# MotorSurucu.net
KiCad netlist of a schematic drawn in Altium Designer
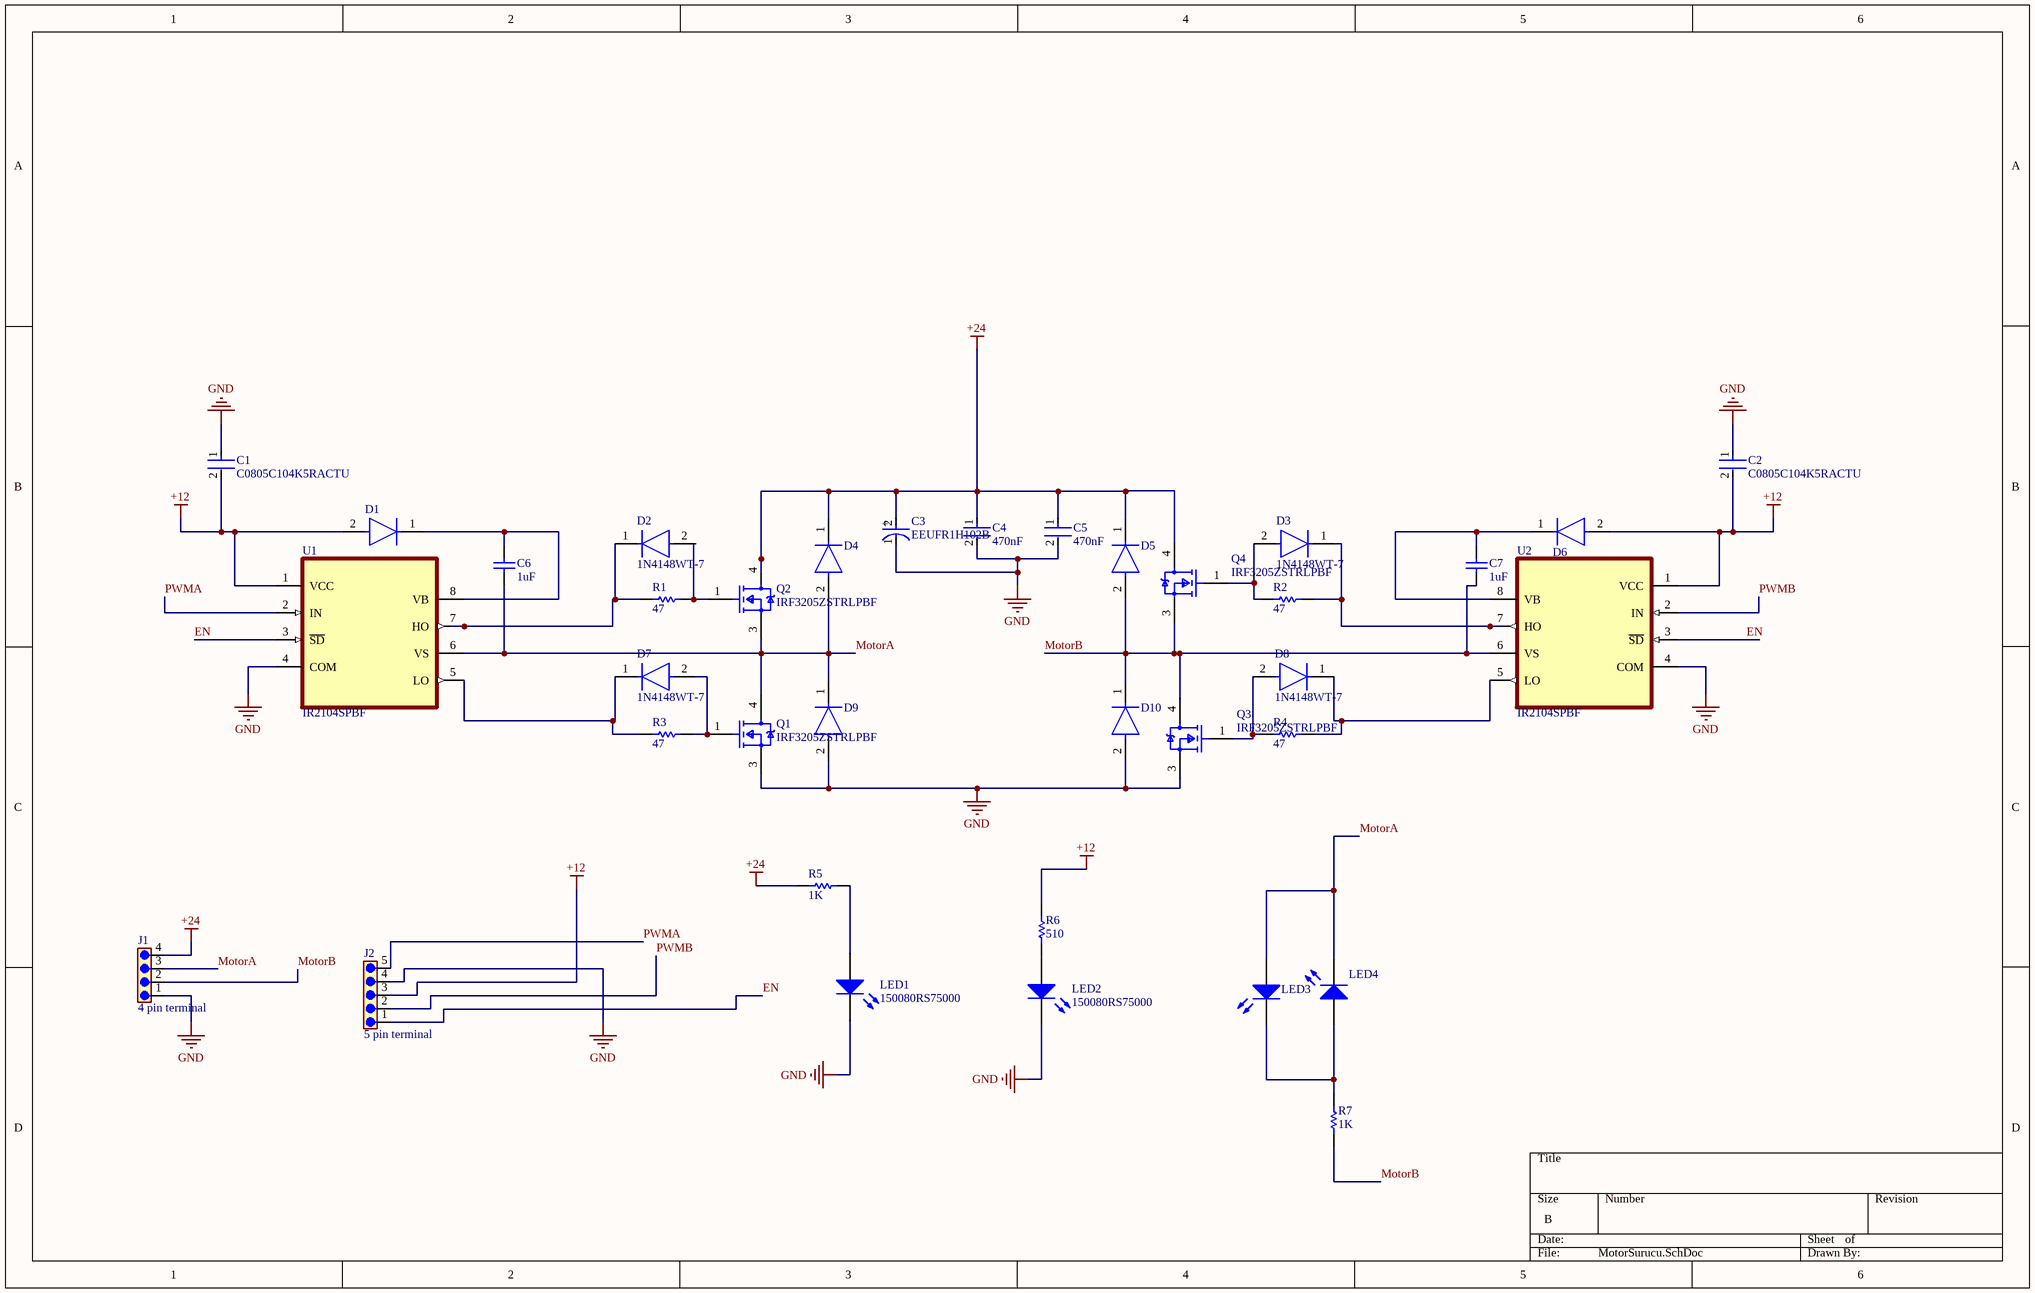
[diagram p0: MotorSurucu.SchDoc]

(export (version "E")
  (design (tool "Eeschema 10.0.6"))
  (components
    (comp (ref "C1")
      (value "C0805C104K5RACTU")
      (footprint "FP-C0805C-DN-MFG")
      (description "CAP CER 0.1UF 50V X7R 0805")
      (fields
        (field (name "MANUFACTURER") "KEMET")
        (field (name "OCTOPART") "https://octopart.com/c0805c104k5ractu-kemet-143926")
      )
      (libsource (lib "Altium Content Vault") (part "b4654b650e69147ec39a6b967a45e02"))
    )
    (comp (ref "C2")
      (value "C0805C104K5RACTU")
      (footprint "FP-C0805C-DN-MFG")
      (description "CAP CER 0.1UF 50V X7R 0805")
      (fields
        (field (name "MANUFACTURER") "KEMET")
        (field (name "OCTOPART") "https://octopart.com/c0805c104k5ractu-kemet-143926")
      )
      (libsource (lib "Altium Content Vault") (part "b4654b650e69147ec39a6b967a45e02"))
    )
    (comp (ref "C3")
      (value "EEUFR1H102B")
      (footprint "FP-RAD-TH-D_16_0_5-L_25_2-MFG")
      (description "Aluminum Electrolytic Capacitors (Radial Lead Type) 1000uF ±20% 50V")
      (fields (field (name "TOLERANCE") "20%"))
      (libsource (lib "Altium Content Vault") (part "203bc49f2ac43e59fd269a8c329ed05"))
    )
    (comp (ref "C4")
      (value "470nF")
      (footprint "FP-C0805C-DN-MFG")
      (description "CAP CER 0.47UF 50V 10% X7R 0805 C0805C474K5RACTU")
      (fields
        (field (name "MANUFACTURER") "KEMET")
        (field (name "MANUFACTURER PART NUMBER") "C0805C474K5RACTU")
      )
      (libsource (lib "Altium Content Vault") (part "b4654b650e69147ec39a6b967a45e02"))
    )
    (comp (ref "C5")
      (value "470nF")
      (footprint "FP-C0805C-DN-MFG")
      (description "CAP CER 0.47UF 50V 10% X7R 0805 C0805C474K5RACTU")
      (fields
        (field (name "MANUFACTURER") "KEMET")
        (field (name "MANUFACTURER PART NUMBER") "C0805C474K5RACTU")
      )
      (libsource (lib "Altium Content Vault") (part "b4654b650e69147ec39a6b967a45e02"))
    )
    (comp (ref "C6")
      (value "1uF")
      (footprint "CAPC2013X135X45LL10T25")
      (description "GRM21BR71H105KA12L")
      (fields (field (name "MANUFACTURER") "Murata"))
      (libsource (lib "Altium Content Vault") (part "CAP"))
    )
    (comp (ref "C7")
      (value "1uF")
      (footprint "CAPC2013X135X45LL10T25")
      (description "GRM21BR71H105KA12L    0805")
      (fields (field (name "MANUFACTURER") "Murata") (field (name "PART NUMBER") "GRM21BR71H105KA12L"))
      (libsource (lib "Altium Content Vault") (part "CAP"))
    )
    (comp (ref "D1")
      (value "1N5819HW1-7-F")
      (footprint "FP-SOD123F_Type_B-MFG")
      (description "DIODE SBR 40V 1A SOD123F")
      (fields
        (field (name "MANUFACTURER") "Diodes Inc.")
        (field (name "OCTOPART") "https://octopart.com/1n5819hw1-7-f-diodes+inc.-67250096")
      )
      (libsource (lib "Altium Content Vault") (part "d7152d700b627762746794eb795d46e"))
    )
    (comp (ref "D2")
      (value "1N4148WT-7")
      (footprint "FP-SOD523-MFG")
      (description "DIODE GEN PURP 80V 125MA SOD523")
      (libsource (lib "Altium Content Vault") (part "d7152d700b627762746794eb795d46e"))
    )
    (comp (ref "D3")
      (value "1N4148WT-7")
      (footprint "FP-SOD523-MFG")
      (description "DIODE GEN PURP 80V 125MA SOD523")
      (libsource (lib "Altium Content Vault") (part "d7152d700b627762746794eb795d46e"))
    )
    (comp (ref "D4")
      (value "1N5819HW1-7-F")
      (footprint "FP-SOD123F_Type_B-MFG")
      (description "DIODE SBR 40V 1A SOD123F")
      (fields
        (field (name "MANUFACTURER") "Diodes Inc.")
        (field (name "OCTOPART") "https://octopart.com/1n5819hw1-7-f-diodes+inc.-67250096")
      )
      (libsource (lib "Altium Content Vault") (part "d7152d700b627762746794eb795d46e"))
    )
    (comp (ref "D5")
      (value "1N5819HW1-7-F")
      (footprint "FP-SOD123F_Type_B-MFG")
      (description "DIODE SBR 40V 1A SOD123F")
      (fields
        (field (name "MANUFACTURER") "Diodes Inc.")
        (field (name "OCTOPART") "https://octopart.com/1n5819hw1-7-f-diodes+inc.-67250096")
      )
      (libsource (lib "Altium Content Vault") (part "d7152d700b627762746794eb795d46e"))
    )
    (comp (ref "D6")
      (value "1N5819HW1-7-F")
      (footprint "FP-SOD123F_Type_B-MFG")
      (description "DIODE SBR 40V 1A SOD123F")
      (fields
        (field (name "MANUFACTURER") "Diodes Inc.")
        (field (name "OCTOPART") "https://octopart.com/1n5819hw1-7-f-diodes+inc.-67250096")
      )
      (libsource (lib "Altium Content Vault") (part "d7152d700b627762746794eb795d46e"))
    )
    (comp (ref "D7")
      (value "1N4148WT-7")
      (footprint "FP-SOD523-MFG")
      (description "DIODE GEN PURP 80V 125MA SOD523")
      (libsource (lib "Altium Content Vault") (part "d7152d700b627762746794eb795d46e"))
    )
    (comp (ref "D8")
      (value "1N4148WT-7")
      (footprint "FP-SOD523-MFG")
      (description "DIODE GEN PURP 80V 125MA SOD523")
      (libsource (lib "Altium Content Vault") (part "d7152d700b627762746794eb795d46e"))
    )
    (comp (ref "D9")
      (value "1N5819HW1-7-F")
      (footprint "FP-SOD123F_Type_B-MFG")
      (description "DIODE SBR 40V 1A SOD123F")
      (fields
        (field (name "MANUFACTURER") "Diodes Inc.")
        (field (name "OCTOPART") "https://octopart.com/1n5819hw1-7-f-diodes+inc.-67250096")
      )
      (libsource (lib "Altium Content Vault") (part "d7152d700b627762746794eb795d46e"))
    )
    (comp (ref "D10")
      (value "1N5819HW1-7-F")
      (footprint "FP-SOD123F_Type_B-MFG")
      (description "DIODE SBR 40V 1A SOD123F")
      (fields
        (field (name "MANUFACTURER") "Diodes Inc.")
        (field (name "OCTOPART") "https://octopart.com/1n5819hw1-7-f-diodes+inc.-67250096")
      )
      (libsource (lib "Altium Content Vault") (part "d7152d700b627762746794eb795d46e"))
    )
    (comp (ref "J1")
      (value "4 pin terminal")
      (footprint "yesil klemens disi")
      (description "WR-TBL SERIES 3055_5.08 MM_PCB H")
      (fields (field (name "MF") "WÃ¼rth Elektronik") (field (name "MP") "691305530004"))
      (libsource (lib "Yildiz_Rover") (part "yesil klemens disi"))
    )
    (comp (ref "J2")
      (value "5 pin terminal")
      (footprint "5li klemens disi")
      (libsource (lib "Yildiz_Rover") (part "5li klemens disi"))
    )
    (comp (ref "LED1")
      (value "150080RS75000")
      (footprint "0805_A")
      (description "SMD mono-color Chip LED, WL-SMCW, Red")
      (fields (field (name "MANUFACTURER") "Wuerth Elektronik"))
      (libsource (lib "Altium Content Vault") (part "WE-LED_K1A2-2"))
    )
    (comp (ref "LED2")
      (value "150080RS75000")
      (footprint "0805_A")
      (description "SMD mono-color Chip LED, WL-SMCW, Red")
      (fields (field (name "MANUFACTURER") "Wuerth Elektronik"))
      (libsource (lib "Altium Content Vault") (part "WE-LED_K1A2-2"))
    )
    (comp (ref "LED3")
      (value "150080BS75000")
      (footprint "0805_A")
      (description "SMD mono-color Chip LED, WL-SMCW, Blue")
      (fields (field (name "MANUFACTURER") "Wuerth Elektronik"))
      (libsource (lib "Altium Content Vault") (part "WE-LED_K1A2-2"))
    )
    (comp (ref "LED4")
      (value "150080BS75000")
      (footprint "0805_A")
      (description "SMD mono-color Chip LED, WL-SMCW, Blue")
      (fields (field (name "MANUFACTURER") "Wuerth Elektronik"))
      (libsource (lib "Altium Content Vault") (part "WE-LED_K1A2-2"))
    )
    (comp (ref "Q1")
      (value "IRF3205ZSTRLPBF")
      (footprint "FP-PG-TO263-3-MFG")
      (description "MOSFET N-CH 55V 75A D2PAK")
      (libsource (lib "Altium Content Vault") (part "99da77bd2200f959409134b3329ebff"))
    )
    (comp (ref "Q2")
      (value "IRF3205ZSTRLPBF")
      (footprint "FP-PG-TO263-3-MFG")
      (description "MOSFET N-CH 55V 75A D2PAK")
      (libsource (lib "Altium Content Vault") (part "99da77bd2200f959409134b3329ebff"))
    )
    (comp (ref "Q3")
      (value "IRF3205ZSTRLPBF")
      (footprint "FP-PG-TO263-3-MFG")
      (description "MOSFET N-CH 55V 75A D2PAK")
      (libsource (lib "Altium Content Vault") (part "99da77bd2200f959409134b3329ebff"))
    )
    (comp (ref "Q4")
      (value "IRF3205ZSTRLPBF")
      (footprint "FP-PG-TO263-3-MFG")
      (description "MOSFET N-CH 55V 75A D2PAK")
      (libsource (lib "Altium Content Vault") (part "99da77bd2200f959409134b3329ebff"))
    )
    (comp (ref "R1")
      (value "47")
      (footprint "RESC2013X70X40NL20T20")
      (description "ERJ6ENF47R0V")
      (fields (field (name "MANUFACTURER") "Panasonic"))
      (libsource (lib "Altium Content Vault") (part "RES"))
    )
    (comp (ref "R2")
      (value "47")
      (footprint "RESC2013X70X40NL20T20")
      (description "ERJ6ENF47R0V")
      (fields (field (name "MANUFACTURER") "Panasonic"))
      (libsource (lib "Altium Content Vault") (part "RES"))
    )
    (comp (ref "R3")
      (value "47")
      (footprint "RESC2013X70X40NL20T20")
      (description "ERJ6ENF47R0V")
      (fields (field (name "MANUFACTURER") "Panasonic"))
      (libsource (lib "Altium Content Vault") (part "RES"))
    )
    (comp (ref "R4")
      (value "47")
      (footprint "RESC2013X70X40NL20T20")
      (description "ERJ6ENF47R0V")
      (fields (field (name "MANUFACTURER") "Panasonic"))
      (libsource (lib "Altium Content Vault") (part "RES"))
    )
    (comp (ref "R5")
      (value "1K")
      (footprint "RESC2013X50X30NL20T20")
      (description "CRCW08051K00FKEA")
      (fields (field (name "MANUFACTURER") "Vishay Dale"))
      (libsource (lib "Altium Content Vault") (part "RES"))
    )
    (comp (ref "R6")
      (value "510")
      (footprint "RESC2013X60X40LL20T25")
      (fields (field (name "MANUFACTURER") "Panasonic") (field (name "PART NUMBER") "ERA6AEB511V"))
      (libsource (lib "Altium Content Vault") (part "RES"))
    )
    (comp (ref "R7")
      (value "1K")
      (footprint "RESC2013X50X30NL20T20")
      (description "CRCW08051K00FKEA")
      (fields (field (name "MANUFACTURER") "Vishay Dale"))
      (libsource (lib "Altium Content Vault") (part "RES"))
    )
    (comp (ref "U1") (value "IR2104SPBF") (footprint "IR2104") (libsource (lib "Schlib1") (part "IR2104")))
    (comp (ref "U2") (value "IR2104SPBF") (footprint "IR2104") (libsource (lib "") (part "IR2104_1")))
  )
  (nets
    (net (code "1") (name "+12") (class "Default")
      (node (ref "C1") (pin "2") (pinfunction "2_2") (pintype "passive"))
      (node (ref "C2") (pin "2") (pinfunction "2_2") (pintype "passive"))
      (node (ref "D1") (pin "2") (pinfunction "A_2") (pintype "passive"))
      (node (ref "D6") (pin "2") (pinfunction "A_2") (pintype "passive"))
      (node (ref "J2") (pin "3") (pinfunction "3_3") (pintype "passive"))
      (node (ref "R6") (pin "1") (pinfunction "1_1") (pintype "passive"))
      (node (ref "U1") (pin "1") (pinfunction "VCC_1") (pintype "power_in"))
      (node (ref "U2") (pin "1") (pinfunction "VCC_1") (pintype "power_in"))
    )
    (net (code "2") (name "+24") (class "Default")
      (node (ref "C3") (pin "2") (pinfunction "A_2") (pintype "passive"))
      (node (ref "C4") (pin "1") (pinfunction "1_1") (pintype "passive"))
      (node (ref "C5") (pin "1") (pinfunction "1_1") (pintype "passive"))
      (node (ref "D4") (pin "1") (pinfunction "C_1") (pintype "passive"))
      (node (ref "D5") (pin "1") (pinfunction "C_1") (pintype "passive"))
      (node (ref "J1") (pin "4") (pinfunction "4_4") (pintype "passive"))
      (node (ref "Q2") (pin "4") (pinfunction "D_4") (pintype "passive"))
      (node (ref "Q4") (pin "4") (pinfunction "D_4") (pintype "passive"))
      (node (ref "R5") (pin "1") (pinfunction "1_1") (pintype "passive"))
    )
    (net (code "3") (name "/EN") (class "Default")
      (node (ref "J2") (pin "1") (pinfunction "1_1") (pintype "passive"))
      (node (ref "U1") (pin "3") (pinfunction "~{SD}_3") (pintype "input"))
      (node (ref "U2") (pin "3") (pinfunction "~{SD}_3") (pintype "input"))
    )
    (net (code "4") (name "/MotorA") (class "Default")
      (node (ref "C6") (pin "1") (pinfunction "1_1") (pintype "passive"))
      (node (ref "D4") (pin "2") (pinfunction "A_2") (pintype "passive"))
      (node (ref "D9") (pin "1") (pinfunction "C_1") (pintype "passive"))
      (node (ref "J1") (pin "3") (pinfunction "3_3") (pintype "passive"))
      (node (ref "LED3") (pin "2") (pinfunction "A_2") (pintype "passive"))
      (node (ref "LED4") (pin "1") (pinfunction "K_1") (pintype "passive"))
      (node (ref "Q1") (pin "4") (pinfunction "D_4") (pintype "passive"))
      (node (ref "Q2") (pin "3") (pinfunction "S_3") (pintype "passive"))
      (node (ref "U1") (pin "6") (pinfunction "VS_6") (pintype "power_in"))
    )
    (net (code "5") (name "/MotorB") (class "Default")
      (node (ref "C7") (pin "1") (pinfunction "1_1") (pintype "passive"))
      (node (ref "D10") (pin "1") (pinfunction "C_1") (pintype "passive"))
      (node (ref "D5") (pin "2") (pinfunction "A_2") (pintype "passive"))
      (node (ref "J1") (pin "2") (pinfunction "2_2") (pintype "passive"))
      (node (ref "Q3") (pin "4") (pinfunction "D_4") (pintype "passive"))
      (node (ref "Q4") (pin "3") (pinfunction "S_3") (pintype "passive"))
      (node (ref "R7") (pin "1") (pinfunction "1_1") (pintype "passive"))
      (node (ref "U2") (pin "6") (pinfunction "VS_6") (pintype "power_in"))
    )
    (net (code "6") (name "/PWMA") (class "Default")
      (node (ref "J2") (pin "5") (pinfunction "5_5") (pintype "passive"))
      (node (ref "U1") (pin "2") (pinfunction "IN_2") (pintype "input"))
    )
    (net (code "7") (name "/PWMB") (class "Default")
      (node (ref "J2") (pin "2") (pinfunction "2_2") (pintype "passive"))
      (node (ref "U2") (pin "2") (pinfunction "IN_2") (pintype "input"))
    )
    (net (code "8") (name "GND") (class "Default")
      (node (ref "C1") (pin "1") (pinfunction "1_1") (pintype "passive"))
      (node (ref "C2") (pin "1") (pinfunction "1_1") (pintype "passive"))
      (node (ref "C3") (pin "1") (pinfunction "C_1") (pintype "passive"))
      (node (ref "C4") (pin "2") (pinfunction "2_2") (pintype "passive"))
      (node (ref "C5") (pin "2") (pinfunction "2_2") (pintype "passive"))
      (node (ref "D10") (pin "2") (pinfunction "A_2") (pintype "passive"))
      (node (ref "D9") (pin "2") (pinfunction "A_2") (pintype "passive"))
      (node (ref "J1") (pin "1") (pinfunction "1_1") (pintype "passive"))
      (node (ref "J2") (pin "4") (pinfunction "4_4") (pintype "passive"))
      (node (ref "LED1") (pin "1") (pinfunction "K_1") (pintype "passive"))
      (node (ref "LED2") (pin "1") (pinfunction "K_1") (pintype "passive"))
      (node (ref "Q1") (pin "3") (pinfunction "S_3") (pintype "passive"))
      (node (ref "Q3") (pin "3") (pinfunction "S_3") (pintype "passive"))
      (node (ref "U1") (pin "4") (pinfunction "COM_4") (pintype "passive"))
      (node (ref "U2") (pin "4") (pinfunction "COM_4") (pintype "passive"))
    )
    (net (code "9") (name "Net-(D1-C)") (class "Default")
      (node (ref "C6") (pin "2") (pinfunction "2_2") (pintype "passive"))
      (node (ref "D1") (pin "1") (pinfunction "C_1") (pintype "passive"))
      (node (ref "U1") (pin "8") (pinfunction "VB_8") (pintype "power_in"))
    )
    (net (code "10") (name "Net-(D2-A)") (class "Default")
      (node (ref "D2") (pin "2") (pinfunction "A_2") (pintype "passive"))
      (node (ref "Q2") (pin "1") (pinfunction "G_1") (pintype "passive"))
      (node (ref "R1") (pin "2") (pinfunction "2_2") (pintype "passive"))
    )
    (net (code "11") (name "Net-(D2-C)") (class "Default")
      (node (ref "D2") (pin "1") (pinfunction "C_1") (pintype "passive"))
      (node (ref "R1") (pin "1") (pinfunction "1_1") (pintype "passive"))
      (node (ref "U1") (pin "7") (pinfunction "HO_7") (pintype "output"))
    )
    (net (code "12") (name "Net-(D3-A)") (class "Default")
      (node (ref "D3") (pin "2") (pinfunction "A_2") (pintype "passive"))
      (node (ref "Q4") (pin "1") (pinfunction "G_1") (pintype "passive"))
      (node (ref "R2") (pin "1") (pinfunction "1_1") (pintype "passive"))
    )
    (net (code "13") (name "Net-(D3-C)") (class "Default")
      (node (ref "D3") (pin "1") (pinfunction "C_1") (pintype "passive"))
      (node (ref "R2") (pin "2") (pinfunction "2_2") (pintype "passive"))
      (node (ref "U2") (pin "7") (pinfunction "HO_7") (pintype "output"))
    )
    (net (code "14") (name "Net-(D6-C)") (class "Default")
      (node (ref "C7") (pin "2") (pinfunction "2_2") (pintype "passive"))
      (node (ref "D6") (pin "1") (pinfunction "C_1") (pintype "passive"))
      (node (ref "U2") (pin "8") (pinfunction "VB_8") (pintype "power_in"))
    )
    (net (code "15") (name "Net-(D7-A)") (class "Default")
      (node (ref "D7") (pin "2") (pinfunction "A_2") (pintype "passive"))
      (node (ref "Q1") (pin "1") (pinfunction "G_1") (pintype "passive"))
      (node (ref "R3") (pin "2") (pinfunction "2_2") (pintype "passive"))
    )
    (net (code "16") (name "Net-(D7-C)") (class "Default")
      (node (ref "D7") (pin "1") (pinfunction "C_1") (pintype "passive"))
      (node (ref "R3") (pin "1") (pinfunction "1_1") (pintype "passive"))
      (node (ref "U1") (pin "5") (pinfunction "LO_5") (pintype "output"))
    )
    (net (code "17") (name "Net-(D8-A)") (class "Default")
      (node (ref "D8") (pin "2") (pinfunction "A_2") (pintype "passive"))
      (node (ref "Q3") (pin "1") (pinfunction "G_1") (pintype "passive"))
      (node (ref "R4") (pin "1") (pinfunction "1_1") (pintype "passive"))
    )
    (net (code "18") (name "Net-(D8-C)") (class "Default")
      (node (ref "D8") (pin "1") (pinfunction "C_1") (pintype "passive"))
      (node (ref "R4") (pin "2") (pinfunction "2_2") (pintype "passive"))
      (node (ref "U2") (pin "5") (pinfunction "LO_5") (pintype "output"))
    )
    (net (code "19") (name "Net-(LED1-A)") (class "Default")
      (node (ref "LED1") (pin "2") (pinfunction "A_2") (pintype "passive"))
      (node (ref "R5") (pin "2") (pinfunction "2_2") (pintype "passive"))
    )
    (net (code "20") (name "Net-(LED2-A)") (class "Default")
      (node (ref "LED2") (pin "2") (pinfunction "A_2") (pintype "passive"))
      (node (ref "R6") (pin "2") (pinfunction "2_2") (pintype "passive"))
    )
    (net (code "21") (name "Net-(LED3-K)") (class "Default")
      (node (ref "LED3") (pin "1") (pinfunction "K_1") (pintype "passive"))
      (node (ref "LED4") (pin "2") (pinfunction "A_2") (pintype "passive"))
      (node (ref "R7") (pin "2") (pinfunction "2_2") (pintype "passive"))
    )
  )
)
